# NNLightSwitcher_power.net
KiCad netlist of a schematic drawn in Altium Designer
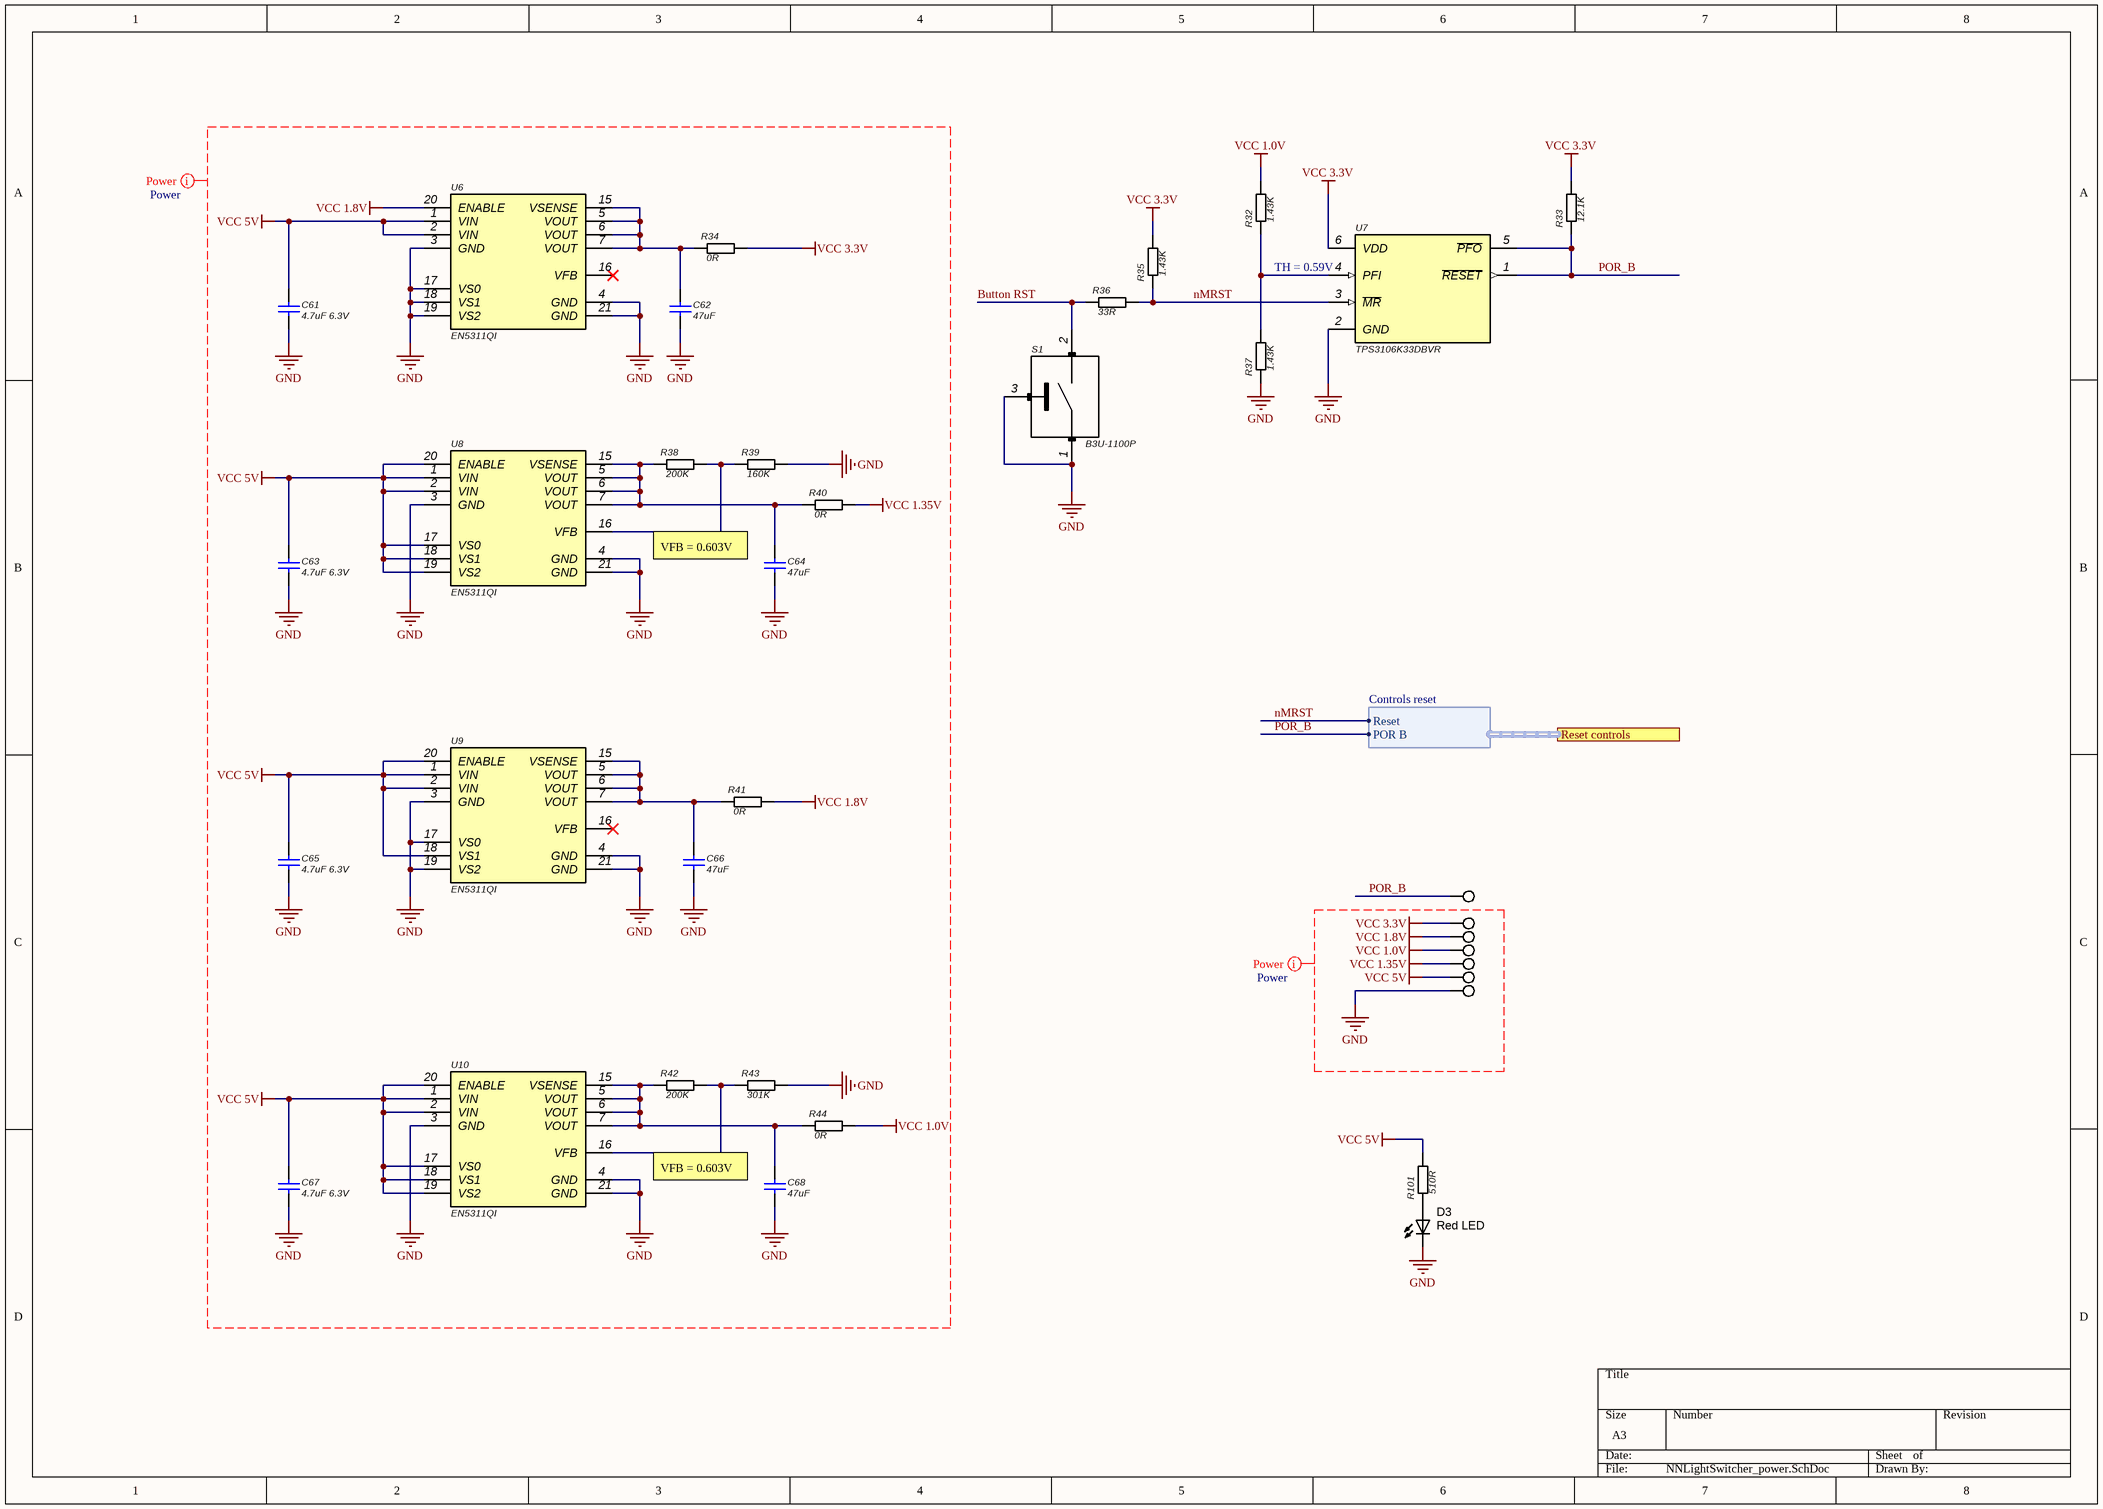
[diagram p0: NNLightSwitcher_power.SchDoc]

(export (version "E")
  (design (tool "Eeschema 10.0.6"))
  (components
    (comp (ref "C61")
      (value "4.7uF 6.3V")
      (footprint "*0603")
      (libsource (lib "NNLightSwitcher") (part "Capacitor 4.7uF 6.3V"))
    )
    (comp (ref "C62")
      (value "47uF")
      (footprint "Res_0805")
      (libsource (lib "NNLightSwitcher") (part "Capacitor 47uF"))
    )
    (comp (ref "C63")
      (value "4.7uF 6.3V")
      (footprint "*0603")
      (libsource (lib "NNLightSwitcher") (part "Capacitor 4.7uF 6.3V"))
    )
    (comp (ref "C64")
      (value "47uF")
      (footprint "Res_0805")
      (libsource (lib "NNLightSwitcher") (part "Capacitor 47uF"))
    )
    (comp (ref "C65")
      (value "4.7uF 6.3V")
      (footprint "*0603")
      (libsource (lib "NNLightSwitcher") (part "Capacitor 4.7uF 6.3V"))
    )
    (comp (ref "C66")
      (value "47uF")
      (footprint "Res_0805")
      (libsource (lib "NNLightSwitcher") (part "Capacitor 47uF"))
    )
    (comp (ref "C67")
      (value "4.7uF 6.3V")
      (footprint "*0603")
      (libsource (lib "NNLightSwitcher") (part "Capacitor 4.7uF 6.3V"))
    )
    (comp (ref "C68")
      (value "47uF")
      (footprint "Res_0805")
      (libsource (lib "NNLightSwitcher") (part "Capacitor 47uF"))
    )
    (comp (ref "D3")
      (value "Red LED")
      (footprint "*LED_SML-P11UTT86R_SML-P11MTT86(Primary)")
      (description "LED red 0402")
      (libsource (lib "NNLightSwitcher") (part "APHHS1005SURCK"))
    )
    (comp (ref "R32")
      (value "1.43K")
      (footprint "0402")
      (libsource (lib "NNLightSwitcher") (part "Resistor 1.43K"))
    )
    (comp (ref "R33")
      (value "12.1K")
      (footprint "0402")
      (libsource (lib "NNLightSwitcher") (part "Resistor 12.1K"))
    )
    (comp (ref "R34")
      (value "0R")
      (footprint "0402")
      (libsource (lib "NNLightSwitcher") (part "Resistor 0R"))
    )
    (comp (ref "R35")
      (value "1.43K")
      (footprint "0402")
      (libsource (lib "NNLightSwitcher") (part "Resistor 1.43K"))
    )
    (comp (ref "R36")
      (value "33R")
      (footprint "0402")
      (libsource (lib "NNLightSwitcher") (part "Resistor 33R"))
    )
    (comp (ref "R37")
      (value "1.43K")
      (footprint "0402")
      (libsource (lib "NNLightSwitcher") (part "Resistor 1.43K"))
    )
    (comp (ref "R38")
      (value "200K")
      (footprint "0402")
      (libsource (lib "NNLightSwitcher") (part "Resistor 200K"))
    )
    (comp (ref "R39")
      (value "160K")
      (footprint "0402")
      (libsource (lib "NNLightSwitcher") (part "Resistor 160K"))
    )
    (comp (ref "R40")
      (value "0R")
      (footprint "0402")
      (libsource (lib "NNLightSwitcher") (part "Resistor 0R"))
    )
    (comp (ref "R41")
      (value "0R")
      (footprint "0402")
      (libsource (lib "NNLightSwitcher") (part "Resistor 0R"))
    )
    (comp (ref "R42")
      (value "200K")
      (footprint "0402")
      (libsource (lib "NNLightSwitcher") (part "Resistor 200K"))
    )
    (comp (ref "R43")
      (value "301K")
      (footprint "0402")
      (libsource (lib "NNLightSwitcher") (part "Resistor 301K"))
    )
    (comp (ref "R44")
      (value "0R")
      (footprint "0402")
      (libsource (lib "NNLightSwitcher") (part "Resistor 0R"))
    )
    (comp (ref "R101")
      (value "510R")
      (footprint "0402")
      (libsource (lib "NNLightSwitcher") (part "Resistor 510R"))
    )
    (comp (ref "S1")
      (value "B3U-1100P")
      (footprint "*SW_B3U-1100P")
      (description "Switch Tactile N.O. SPST Projected Plunger PC Pins 0.05A 24VDC 1.47N Thru-Hole Bag")
      (libsource (lib "NNLightSwitcher") (part "B3U-1100P"))
    )
    (comp (ref "TP7")
      (value "Test point")
      (footprint "Testpoint_Keystone_Miniature")
      (description "Test Point, Miniature, SMT")
      (libsource (lib "NNLightSwitcher") (part "Test point"))
    )
    (comp (ref "TP8")
      (value "Test point")
      (footprint "Testpoint_with_pad")
      (description "Test Point, Miniature, SMT")
      (libsource (lib "NNLightSwitcher") (part "Test point"))
    )
    (comp (ref "TP9")
      (value "Test point")
      (footprint "Testpoint_with_pad")
      (description "Test Point, Miniature, SMT")
      (libsource (lib "NNLightSwitcher") (part "Test point"))
    )
    (comp (ref "TP10")
      (value "Test point")
      (footprint "Testpoint_with_pad")
      (description "Test Point, Miniature, SMT")
      (libsource (lib "NNLightSwitcher") (part "Test point"))
    )
    (comp (ref "TP11")
      (value "Test point")
      (footprint "Testpoint_Keystone_Miniature")
      (description "Test Point, Miniature, SMT")
      (libsource (lib "NNLightSwitcher") (part "Test point"))
    )
    (comp (ref "TP12")
      (value "Test point")
      (footprint "Testpoint_with_pad")
      (description "Test Point, Miniature, SMT")
      (libsource (lib "NNLightSwitcher") (part "Test point"))
    )
    (comp (ref "TP13")
      (value "Test point")
      (footprint "Testpoint_with_pad")
      (description "Test Point, Miniature, SMT")
      (libsource (lib "NNLightSwitcher") (part "Test point"))
    )
    (comp (ref "U6")
      (value "EN5311QI")
      (footprint "*QFN_20-PIN_ATMEL_20M1")
      (description "1A DC-DC Step-Down Converter")
      (libsource (lib "NNLightSwitcher") (part "EN5311QI"))
    )
    (comp (ref "U7")
      (value "TPS3106K33DBVR")
      (footprint "*SOT95P280X145-6N")
      (description "Ultra Low-Supply Current/Supply-Voltage Supervisory Circuits 6-SOT-23 -40 to 85")
      (fields (field (name "MF") "Texas Instruments"))
      (libsource (lib "NNLightSwitcher") (part "TPS3106K33DBVR"))
    )
    (comp (ref "U8")
      (value "EN5311QI")
      (footprint "*QFN_20-PIN_ATMEL_20M1")
      (description "1A DC-DC Step-Down Converter")
      (libsource (lib "NNLightSwitcher") (part "EN5311QI"))
    )
    (comp (ref "U9")
      (value "EN5311QI")
      (footprint "*QFN_20-PIN_ATMEL_20M1")
      (description "1A DC-DC Step-Down Converter")
      (libsource (lib "NNLightSwitcher") (part "EN5311QI"))
    )
    (comp (ref "U10")
      (value "EN5311QI")
      (footprint "*QFN_20-PIN_ATMEL_20M1")
      (description "1A DC-DC Step-Down Converter")
      (libsource (lib "NNLightSwitcher") (part "EN5311QI"))
    )
  )
  (nets
    (net (code "3") (name "/Button RST") (class "Default")
      (node (ref "R36") (pin "1") (pinfunction "1_1") (pintype "passive"))
      (node (ref "S1") (pin "2") (pinfunction "2_2") (pintype "passive"))
    )
    (net (code "4") (name "/POR_B") (class "Default")
      (node (ref "R33") (pin "1") (pinfunction "1_1") (pintype "passive"))
      (node (ref "TP7") (pin "1") (pintype "passive"))
      (node (ref "U7") (pin "1") (pinfunction "~{RESET}_1") (pintype "output"))
      (node (ref "U7") (pin "5") (pinfunction "~{PFO}_5") (pintype "passive"))
    )
    (net (code "5") (name "/nMRST") (class "Default")
      (node (ref "R35") (pin "1") (pinfunction "1_1") (pintype "passive"))
      (node (ref "R36") (pin "2") (pinfunction "2_2") (pintype "passive"))
      (node (ref "U7") (pin "3") (pinfunction "~{MR}_3") (pintype "input"))
    )
    (net (code "7") (name "GND") (class "Default")
      (node (ref "C61") (pin "2") (pinfunction "2_2") (pintype "passive"))
      (node (ref "C62") (pin "2") (pinfunction "2_2") (pintype "passive"))
      (node (ref "C63") (pin "2") (pinfunction "2_2") (pintype "passive"))
      (node (ref "C64") (pin "2") (pinfunction "2_2") (pintype "passive"))
      (node (ref "C65") (pin "2") (pinfunction "2_2") (pintype "passive"))
      (node (ref "C66") (pin "2") (pinfunction "2_2") (pintype "passive"))
      (node (ref "C67") (pin "2") (pinfunction "2_2") (pintype "passive"))
      (node (ref "C68") (pin "2") (pinfunction "2_2") (pintype "passive"))
      (node (ref "D3") (pin "C") (pinfunction "C_C") (pintype "passive"))
      (node (ref "R37") (pin "1") (pinfunction "1_1") (pintype "passive"))
      (node (ref "R39") (pin "2") (pinfunction "2_2") (pintype "passive"))
      (node (ref "R43") (pin "2") (pinfunction "2_2") (pintype "passive"))
      (node (ref "S1") (pin "1") (pinfunction "1_1") (pintype "passive"))
      (node (ref "S1") (pin "3") (pinfunction "3_3") (pintype "passive"))
      (node (ref "TP13") (pin "1") (pintype "passive"))
      (node (ref "U10") (pin "21") (pinfunction "GND_21") (pintype "power_in"))
      (node (ref "U10") (pin "3") (pinfunction "GND_3") (pintype "power_in"))
      (node (ref "U10") (pin "4") (pinfunction "GND_4") (pintype "power_in"))
      (node (ref "U6") (pin "17") (pinfunction "VS0_17") (pintype "passive"))
      (node (ref "U6") (pin "18") (pinfunction "VS1_18") (pintype "passive"))
      (node (ref "U6") (pin "19") (pinfunction "VS2_19") (pintype "passive"))
      (node (ref "U6") (pin "21") (pinfunction "GND_21") (pintype "power_in"))
      (node (ref "U6") (pin "3") (pinfunction "GND_3") (pintype "power_in"))
      (node (ref "U6") (pin "4") (pinfunction "GND_4") (pintype "power_in"))
      (node (ref "U7") (pin "2") (pinfunction "GND_2") (pintype "passive"))
      (node (ref "U8") (pin "21") (pinfunction "GND_21") (pintype "power_in"))
      (node (ref "U8") (pin "3") (pinfunction "GND_3") (pintype "power_in"))
      (node (ref "U8") (pin "4") (pinfunction "GND_4") (pintype "power_in"))
      (node (ref "U9") (pin "17") (pinfunction "VS0_17") (pintype "passive"))
      (node (ref "U9") (pin "19") (pinfunction "VS2_19") (pintype "passive"))
      (node (ref "U9") (pin "21") (pinfunction "GND_21") (pintype "power_in"))
      (node (ref "U9") (pin "3") (pinfunction "GND_3") (pintype "power_in"))
      (node (ref "U9") (pin "4") (pinfunction "GND_4") (pintype "power_in"))
    )
    (net (code "8") (name "Net-(D3-PadA)") (class "Default")
      (node (ref "D3") (pin "A") (pinfunction "A_A") (pintype "passive"))
      (node (ref "R101") (pin "1") (pinfunction "1_1") (pintype "passive"))
    )
    (net (code "9") (name "Net-(U6-VSENSE)") (class "Default")
      (node (ref "C62") (pin "1") (pinfunction "1_1") (pintype "passive"))
      (node (ref "R34") (pin "1") (pinfunction "1_1") (pintype "passive"))
      (node (ref "U6") (pin "15") (pinfunction "VSENSE_15") (pintype "passive"))
      (node (ref "U6") (pin "5") (pinfunction "VOUT_5") (pintype "passive"))
      (node (ref "U6") (pin "6") (pinfunction "VOUT_6") (pintype "passive"))
      (node (ref "U6") (pin "7") (pinfunction "VOUT_7") (pintype "passive"))
    )
    (net (code "10") (name "Net-(U7-PFI)") (class "Default")
      (node (ref "R32") (pin "1") (pinfunction "1_1") (pintype "passive"))
      (node (ref "R37") (pin "2") (pinfunction "2_2") (pintype "passive"))
      (node (ref "U7") (pin "4") (pinfunction "PFI_4") (pintype "input"))
    )
    (net (code "11") (name "Net-(U8-VFB)") (class "Default")
      (node (ref "R38") (pin "2") (pinfunction "2_2") (pintype "passive"))
      (node (ref "R39") (pin "1") (pinfunction "1_1") (pintype "passive"))
      (node (ref "U8") (pin "16") (pinfunction "VFB_16") (pintype "power_in"))
    )
    (net (code "12") (name "Net-(U8-VSENSE)") (class "Default")
      (node (ref "C64") (pin "1") (pinfunction "1_1") (pintype "passive"))
      (node (ref "R38") (pin "1") (pinfunction "1_1") (pintype "passive"))
      (node (ref "R40") (pin "1") (pinfunction "1_1") (pintype "passive"))
      (node (ref "U8") (pin "15") (pinfunction "VSENSE_15") (pintype "passive"))
      (node (ref "U8") (pin "5") (pinfunction "VOUT_5") (pintype "passive"))
      (node (ref "U8") (pin "6") (pinfunction "VOUT_6") (pintype "passive"))
      (node (ref "U8") (pin "7") (pinfunction "VOUT_7") (pintype "passive"))
    )
    (net (code "13") (name "Net-(U9-VSENSE)") (class "Default")
      (node (ref "C66") (pin "1") (pinfunction "1_1") (pintype "passive"))
      (node (ref "R41") (pin "1") (pinfunction "1_1") (pintype "passive"))
      (node (ref "U9") (pin "15") (pinfunction "VSENSE_15") (pintype "passive"))
      (node (ref "U9") (pin "5") (pinfunction "VOUT_5") (pintype "passive"))
      (node (ref "U9") (pin "6") (pinfunction "VOUT_6") (pintype "passive"))
      (node (ref "U9") (pin "7") (pinfunction "VOUT_7") (pintype "passive"))
    )
    (net (code "14") (name "Net-(U10-VFB)") (class "Default")
      (node (ref "R42") (pin "2") (pinfunction "2_2") (pintype "passive"))
      (node (ref "R43") (pin "1") (pinfunction "1_1") (pintype "passive"))
      (node (ref "U10") (pin "16") (pinfunction "VFB_16") (pintype "power_in"))
    )
    (net (code "15") (name "Net-(U10-VSENSE)") (class "Default")
      (node (ref "C68") (pin "1") (pinfunction "1_1") (pintype "passive"))
      (node (ref "R42") (pin "1") (pinfunction "1_1") (pintype "passive"))
      (node (ref "R44") (pin "1") (pinfunction "1_1") (pintype "passive"))
      (node (ref "U10") (pin "15") (pinfunction "VSENSE_15") (pintype "passive"))
      (node (ref "U10") (pin "5") (pinfunction "VOUT_5") (pintype "passive"))
      (node (ref "U10") (pin "6") (pinfunction "VOUT_6") (pintype "passive"))
      (node (ref "U10") (pin "7") (pinfunction "VOUT_7") (pintype "passive"))
    )
    (net (code "16") (name "VCC 1.0V") (class "Default")
      (node (ref "R32") (pin "2") (pinfunction "2_2") (pintype "passive"))
      (node (ref "R44") (pin "2") (pinfunction "2_2") (pintype "passive"))
      (node (ref "TP10") (pin "1") (pintype "passive"))
    )
    (net (code "17") (name "VCC 1.8V") (class "Default")
      (node (ref "R41") (pin "2") (pinfunction "2_2") (pintype "passive"))
      (node (ref "TP9") (pin "1") (pintype "passive"))
      (node (ref "U6") (pin "20") (pinfunction "ENABLE_20") (pintype "passive"))
    )
    (net (code "18") (name "VCC 1.35V") (class "Default")
      (node (ref "R40") (pin "2") (pinfunction "2_2") (pintype "passive"))
      (node (ref "TP11") (pin "1") (pintype "passive"))
    )
    (net (code "19") (name "VCC 3.3V") (class "Default")
      (node (ref "R33") (pin "2") (pinfunction "2_2") (pintype "passive"))
      (node (ref "R34") (pin "2") (pinfunction "2_2") (pintype "passive"))
      (node (ref "R35") (pin "2") (pinfunction "2_2") (pintype "passive"))
      (node (ref "TP8") (pin "1") (pintype "passive"))
      (node (ref "U7") (pin "6") (pinfunction "VDD_6") (pintype "power_in"))
    )
    (net (code "20") (name "VCC 5V") (class "Default")
      (node (ref "C61") (pin "1") (pinfunction "1_1") (pintype "passive"))
      (node (ref "C63") (pin "1") (pinfunction "1_1") (pintype "passive"))
      (node (ref "C65") (pin "1") (pinfunction "1_1") (pintype "passive"))
      (node (ref "C67") (pin "1") (pinfunction "1_1") (pintype "passive"))
      (node (ref "R101") (pin "2") (pinfunction "2_2") (pintype "passive"))
      (node (ref "TP12") (pin "1") (pintype "passive"))
      (node (ref "U10") (pin "1") (pinfunction "VIN_1") (pintype "passive"))
      (node (ref "U10") (pin "17") (pinfunction "VS0_17") (pintype "passive"))
      (node (ref "U10") (pin "18") (pinfunction "VS1_18") (pintype "passive"))
      (node (ref "U10") (pin "19") (pinfunction "VS2_19") (pintype "passive"))
      (node (ref "U10") (pin "2") (pinfunction "VIN_2") (pintype "passive"))
      (node (ref "U10") (pin "20") (pinfunction "ENABLE_20") (pintype "passive"))
      (node (ref "U6") (pin "1") (pinfunction "VIN_1") (pintype "passive"))
      (node (ref "U6") (pin "2") (pinfunction "VIN_2") (pintype "passive"))
      (node (ref "U8") (pin "1") (pinfunction "VIN_1") (pintype "passive"))
      (node (ref "U8") (pin "17") (pinfunction "VS0_17") (pintype "passive"))
      (node (ref "U8") (pin "18") (pinfunction "VS1_18") (pintype "passive"))
      (node (ref "U8") (pin "19") (pinfunction "VS2_19") (pintype "passive"))
      (node (ref "U8") (pin "2") (pinfunction "VIN_2") (pintype "passive"))
      (node (ref "U8") (pin "20") (pinfunction "ENABLE_20") (pintype "passive"))
      (node (ref "U9") (pin "1") (pinfunction "VIN_1") (pintype "passive"))
      (node (ref "U9") (pin "18") (pinfunction "VS1_18") (pintype "passive"))
      (node (ref "U9") (pin "2") (pinfunction "VIN_2") (pintype "passive"))
      (node (ref "U9") (pin "20") (pinfunction "ENABLE_20") (pintype "passive"))
    )
    (net (code "21") (name "unconnected-(U6-VFB-Pad16)") (class "Default")
      (node (ref "U6") (pin "16") (pinfunction "VFB_16") (pintype "power_in+no_connect"))
    )
    (net (code "22") (name "unconnected-(U9-VFB-Pad16)") (class "Default")
      (node (ref "U9") (pin "16") (pinfunction "VFB_16") (pintype "power_in+no_connect"))
    )
  )
)
